# SCH_Vex-Field-Controller_2025-05-28.net
KiCad netlist of a schematic drawn in EasyEDA
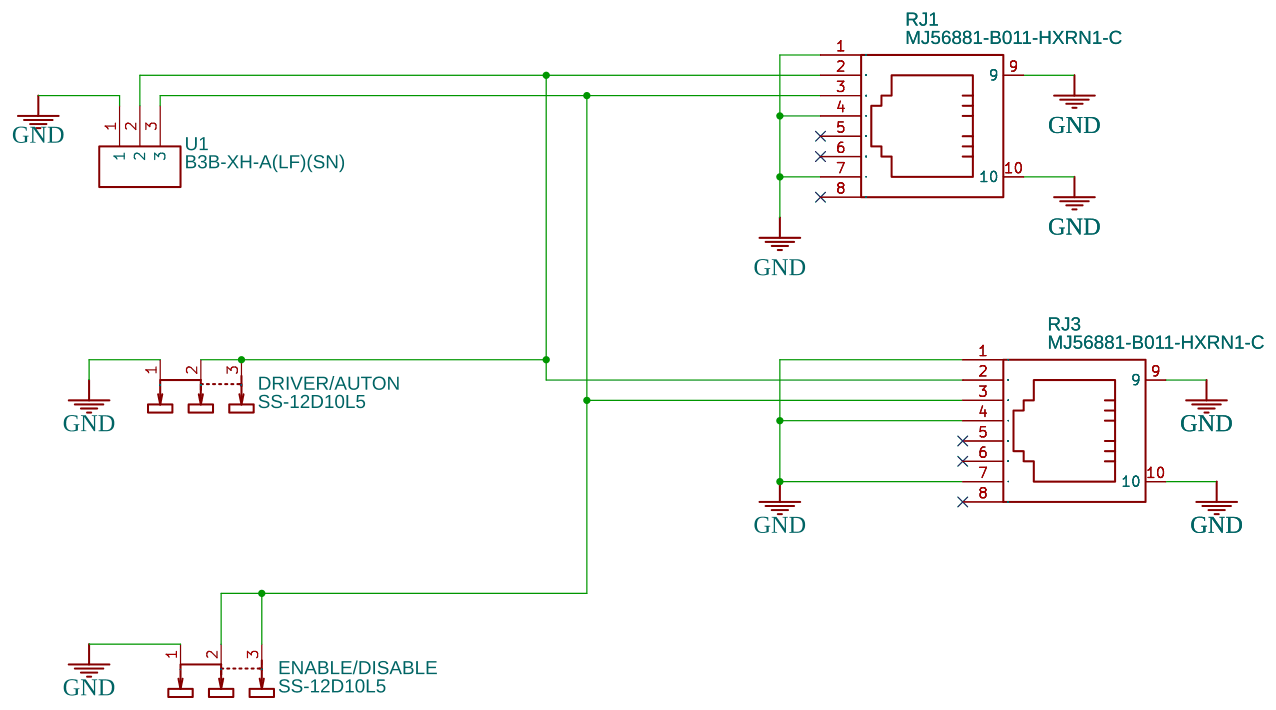
[diagram p0: schematic sheet]

(export (version "E")
  (design (tool "Eeschema 10.0.6"))
  (components
    (comp (ref "DRIVER/AUTON")
      (value "SS-12D10L5")
      (fields (field (name "Manufacturer") "XKB Connectivity(中国星坤)"))
      (libsource (lib "") (part "SS-12D10L5"))
    )
    (comp (ref "ENABLE/DISABLE")
      (value "SS-12D10L5")
      (fields (field (name "Manufacturer") "XKB Connectivity(中国星坤)"))
      (libsource (lib "") (part "SS-12D10L5_1"))
    )
    (comp (ref "RJ1")
      (value "MJ56881-B011-HXRN1-C")
      (fields
        (field (name "Manufacturer Part") "MJ56881-B011-HLRN1-C")
        (field (name "Manufacturer") "Heling(合陵)")
      )
      (libsource (lib "") (part "MJ56881-B011-HXRN1-C"))
    )
    (comp (ref "RJ3")
      (value "MJ56881-B011-HXRN1-C")
      (fields
        (field (name "Manufacturer Part") "MJ56881-B011-HLRN1-C")
        (field (name "Manufacturer") "Heling(合陵)")
      )
      (libsource (lib "") (part "MJ56881-B011-HXRN1-C"))
    )
    (comp (ref "U1")
      (value "B3B-XH-A(LF)(SN)")
      (fields (field (name "Manufacturer") "JST"))
      (libsource (lib "") (part "B3B-XH-A(LF)(SN)"))
    )
  )
  (nets
    (net (code "1") (name "GND") (class "Default")
      (node (ref "DRIVER/AUTON") (pin "1") (pinfunction "1_1") (pintype "unspecified"))
      (node (ref "ENABLE/DISABLE") (pin "1") (pinfunction "1_1") (pintype "unspecified"))
      (node (ref "RJ1") (pin "1") (pinfunction "1_1") (pintype "unspecified"))
      (node (ref "RJ1") (pin "10") (pinfunction "10_10") (pintype "unspecified"))
      (node (ref "RJ1") (pin "4") (pinfunction "4_4") (pintype "unspecified"))
      (node (ref "RJ1") (pin "7") (pinfunction "7_7") (pintype "unspecified"))
      (node (ref "RJ1") (pin "9") (pinfunction "9_9") (pintype "unspecified"))
      (node (ref "RJ3") (pin "1") (pinfunction "1_1") (pintype "unspecified"))
      (node (ref "RJ3") (pin "10") (pinfunction "10_10") (pintype "unspecified"))
      (node (ref "RJ3") (pin "4") (pinfunction "4_4") (pintype "unspecified"))
      (node (ref "RJ3") (pin "7") (pinfunction "7_7") (pintype "unspecified"))
      (node (ref "RJ3") (pin "9") (pinfunction "9_9") (pintype "unspecified"))
      (node (ref "U1") (pin "1") (pinfunction "1_1") (pintype "unspecified"))
    )
    (net (code "2") (name "Net-(DRIVER/AUTON-Pad2)") (class "Default")
      (node (ref "DRIVER/AUTON") (pin "2") (pinfunction "2_2") (pintype "unspecified"))
      (node (ref "DRIVER/AUTON") (pin "3") (pinfunction "3_3") (pintype "unspecified"))
      (node (ref "RJ1") (pin "2") (pinfunction "2_2") (pintype "unspecified"))
      (node (ref "RJ3") (pin "2") (pinfunction "2_2") (pintype "unspecified"))
      (node (ref "U1") (pin "2") (pinfunction "2_2") (pintype "unspecified"))
    )
    (net (code "3") (name "Net-(ENABLE/DISABLE-Pad2)") (class "Default")
      (node (ref "ENABLE/DISABLE") (pin "2") (pinfunction "2_2") (pintype "unspecified"))
      (node (ref "ENABLE/DISABLE") (pin "3") (pinfunction "3_3") (pintype "unspecified"))
      (node (ref "RJ1") (pin "3") (pinfunction "3_3") (pintype "unspecified"))
      (node (ref "RJ3") (pin "3") (pinfunction "3_3") (pintype "unspecified"))
      (node (ref "U1") (pin "3") (pinfunction "3_3") (pintype "unspecified"))
    )
    (net (code "4") (name "unconnected-(RJ1-Pad5)") (class "Default")
      (node (ref "RJ1") (pin "5") (pinfunction "5_5") (pintype "unspecified+no_connect"))
    )
    (net (code "5") (name "unconnected-(RJ1-Pad6)") (class "Default")
      (node (ref "RJ1") (pin "6") (pinfunction "6_6") (pintype "unspecified+no_connect"))
    )
    (net (code "6") (name "unconnected-(RJ1-Pad8)") (class "Default")
      (node (ref "RJ1") (pin "8") (pinfunction "8_8") (pintype "unspecified+no_connect"))
    )
    (net (code "7") (name "unconnected-(RJ3-Pad5)") (class "Default")
      (node (ref "RJ3") (pin "5") (pinfunction "5_5") (pintype "unspecified+no_connect"))
    )
    (net (code "8") (name "unconnected-(RJ3-Pad6)") (class "Default")
      (node (ref "RJ3") (pin "6") (pinfunction "6_6") (pintype "unspecified+no_connect"))
    )
    (net (code "9") (name "unconnected-(RJ3-Pad8)") (class "Default")
      (node (ref "RJ3") (pin "8") (pinfunction "8_8") (pintype "unspecified+no_connect"))
    )
  )
)
